# PHY.net
KiCad netlist of a schematic drawn in Altium Designer
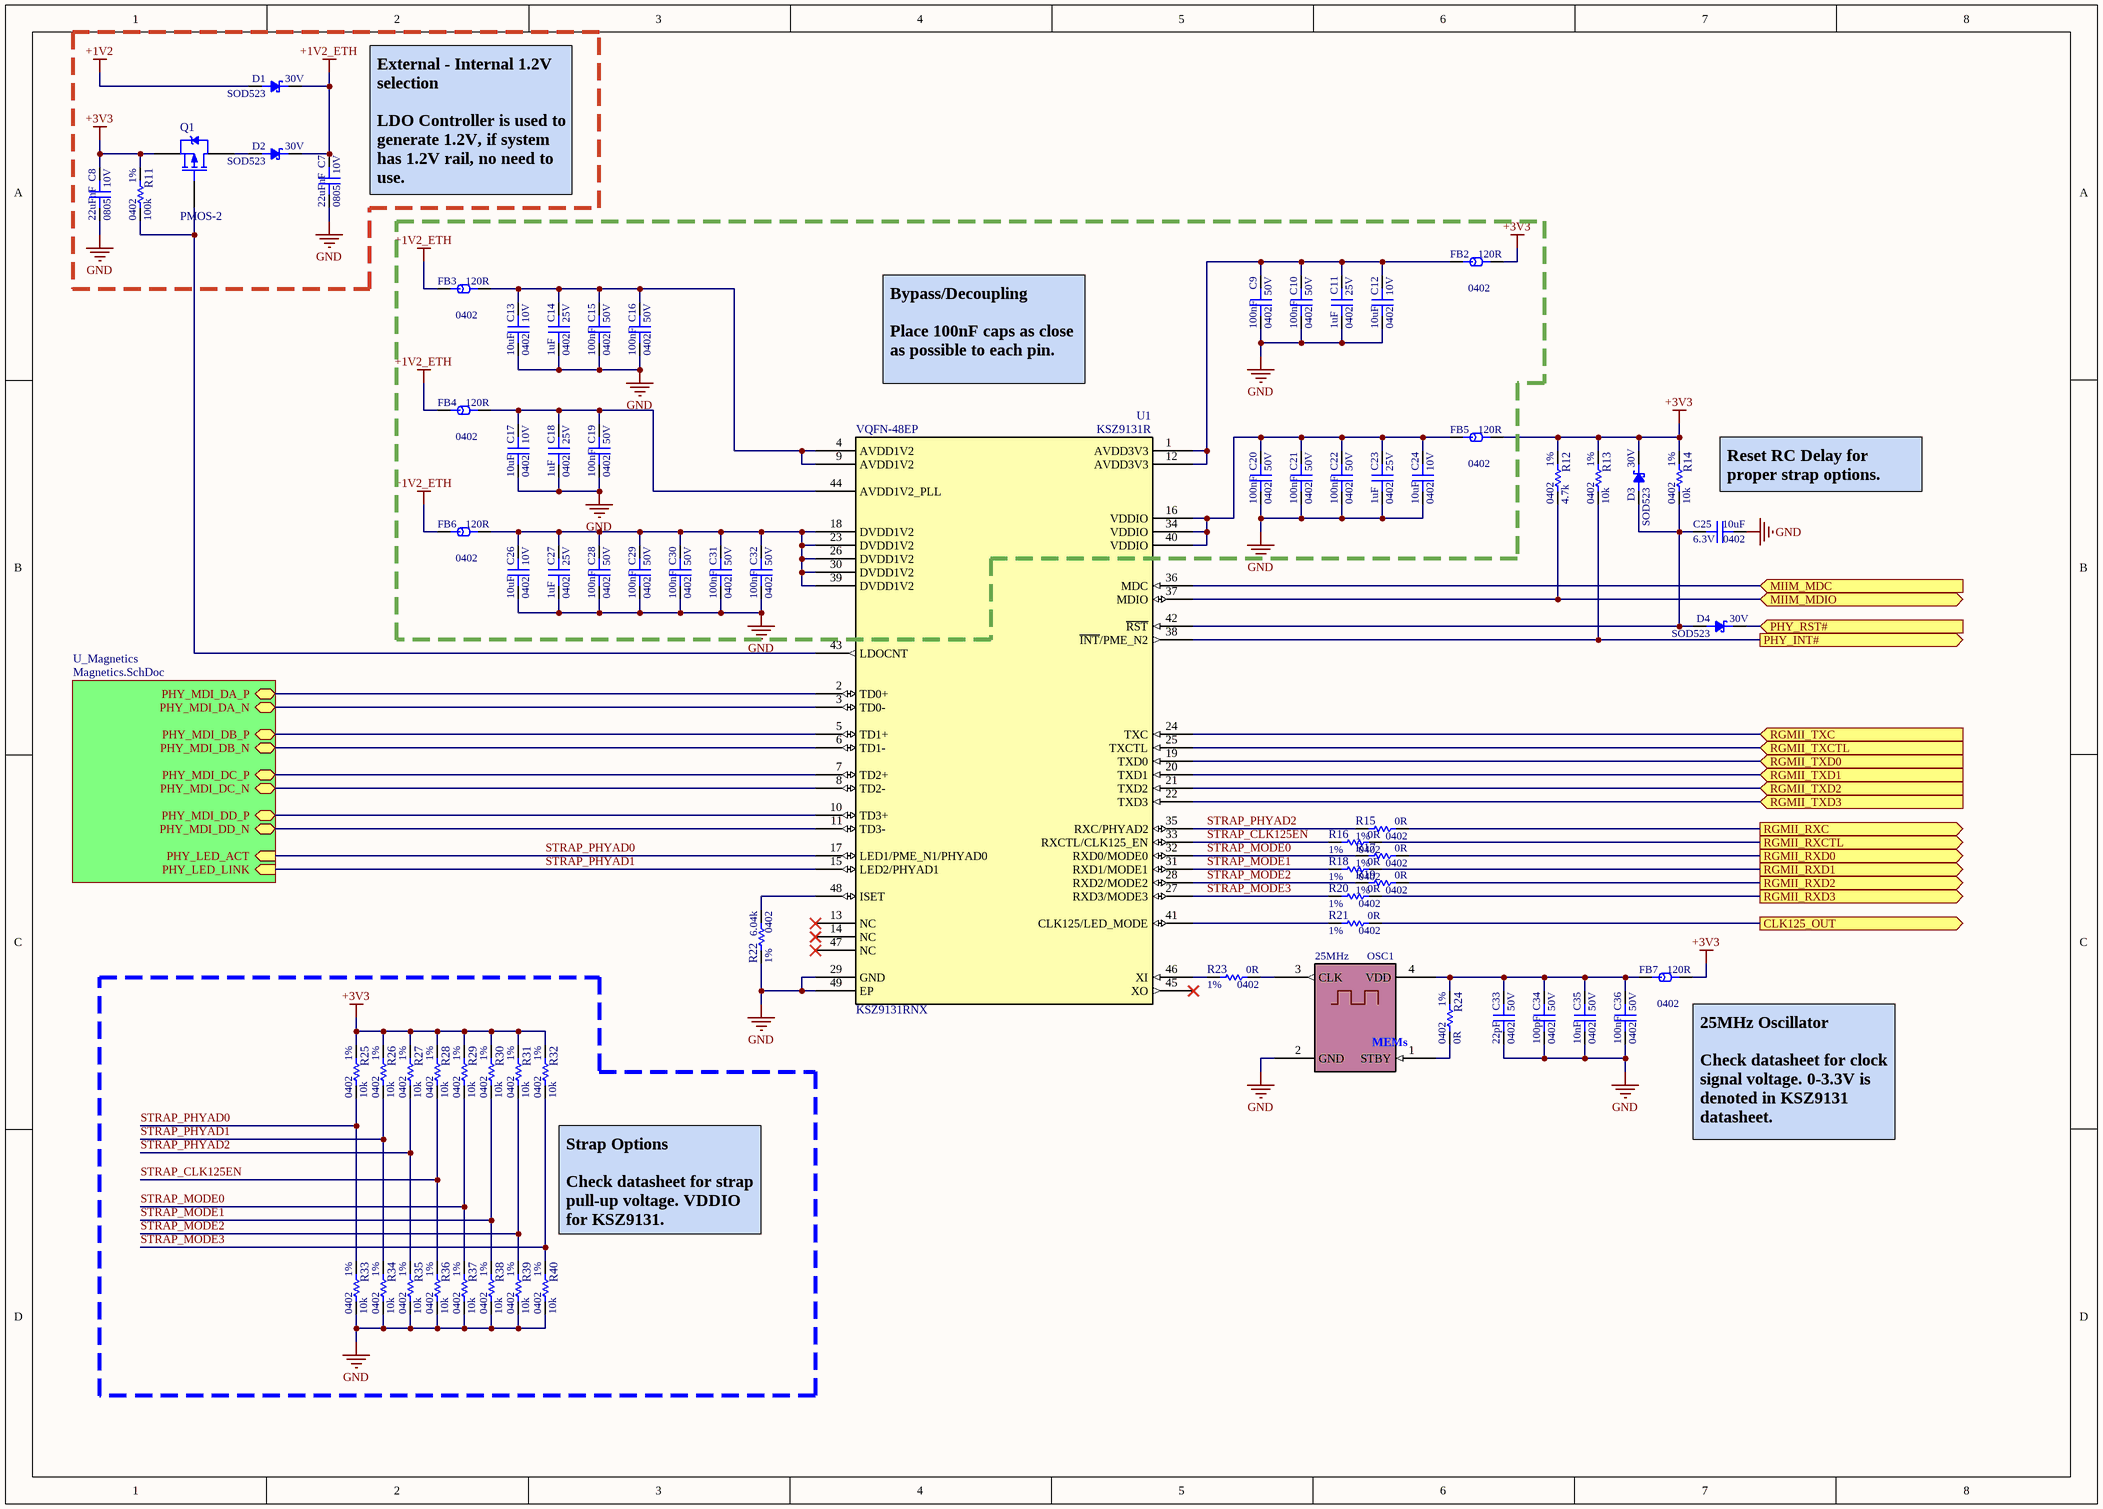
[diagram p0: PHY.SchDoc]

(export (version "E")
  (design (tool "Eeschema 10.0.6"))
  (components
    (comp (ref "C7")
      (value "22uFnF")
      (footprint "C_0402_GEN_0.70H")
      (description "CAP_CER_100nF_50V_X7R_10%_0402")
      (fields
        (field (name "VOLTAGE") "10V")
        (field (name "PACKAGE") "0805")
        (field (name "TOLERANCE") "10%")
        (field (name "Comment") "Capacitor")
      )
      (libsource (lib "BNA_HwLibDB") (part "Capacitor"))
    )
    (comp (ref "C8")
      (value "22uFnF")
      (footprint "C_0402_GEN_0.70H")
      (description "CAP_CER_100nF_50V_X7R_10%_0402")
      (fields
        (field (name "VOLTAGE") "10V")
        (field (name "PACKAGE") "0805")
        (field (name "TOLERANCE") "10%")
        (field (name "Comment") "Capacitor")
      )
      (libsource (lib "BNA_HwLibDB") (part "Capacitor"))
    )
    (comp (ref "C9")
      (value "100nF")
      (footprint "C_0402_GEN_0.70H")
      (description "CAP_CER_100nF_50V_X7R_10%_0402")
      (fields
        (field (name "VOLTAGE") "50V")
        (field (name "PACKAGE") "0402")
        (field (name "TOLERANCE") "10%")
        (field (name "Comment") "Capacitor")
      )
      (libsource (lib "BNA_HwLibDB") (part "Capacitor"))
    )
    (comp (ref "C10")
      (value "100nF")
      (footprint "C_0402_GEN_0.70H")
      (description "CAP_CER_100nF_50V_X7R_10%_0402")
      (fields
        (field (name "VOLTAGE") "50V")
        (field (name "PACKAGE") "0402")
        (field (name "TOLERANCE") "10%")
        (field (name "Comment") "Capacitor")
      )
      (libsource (lib "BNA_HwLibDB") (part "Capacitor"))
    )
    (comp (ref "C11")
      (value "1uF")
      (footprint "C_0402_GEN_0.70H")
      (description "CAP_CER_100nF_50V_X7R_10%_0402")
      (fields
        (field (name "VOLTAGE") "25V")
        (field (name "PACKAGE") "0402")
        (field (name "TOLERANCE") "10%")
        (field (name "Comment") "Capacitor")
      )
      (libsource (lib "BNA_HwLibDB") (part "Capacitor"))
    )
    (comp (ref "C12")
      (value "10uF")
      (footprint "C_0402_GEN_0.70H")
      (description "CAP_CER_100nF_50V_X7R_10%_0402")
      (fields
        (field (name "VOLTAGE") "10V")
        (field (name "PACKAGE") "0402")
        (field (name "TOLERANCE") "10%")
        (field (name "Comment") "Capacitor")
      )
      (libsource (lib "BNA_HwLibDB") (part "Capacitor"))
    )
    (comp (ref "C13")
      (value "10uF")
      (footprint "C_0402_GEN_0.70H")
      (description "CAP_CER_100nF_50V_X7R_10%_0402")
      (fields
        (field (name "VOLTAGE") "10V")
        (field (name "PACKAGE") "0402")
        (field (name "TOLERANCE") "10%")
        (field (name "Comment") "Capacitor")
      )
      (libsource (lib "BNA_HwLibDB") (part "Capacitor"))
    )
    (comp (ref "C14")
      (value "1uF")
      (footprint "C_0402_GEN_0.70H")
      (description "CAP_CER_100nF_50V_X7R_10%_0402")
      (fields
        (field (name "VOLTAGE") "25V")
        (field (name "PACKAGE") "0402")
        (field (name "TOLERANCE") "10%")
        (field (name "Comment") "Capacitor")
      )
      (libsource (lib "BNA_HwLibDB") (part "Capacitor"))
    )
    (comp (ref "C15")
      (value "100nF")
      (footprint "C_0402_GEN_0.70H")
      (description "CAP_CER_100nF_50V_X7R_10%_0402")
      (fields
        (field (name "VOLTAGE") "50V")
        (field (name "PACKAGE") "0402")
        (field (name "TOLERANCE") "10%")
        (field (name "Comment") "Capacitor")
      )
      (libsource (lib "BNA_HwLibDB") (part "Capacitor"))
    )
    (comp (ref "C16")
      (value "100nF")
      (footprint "C_0402_GEN_0.70H")
      (description "CAP_CER_100nF_50V_X7R_10%_0402")
      (fields
        (field (name "VOLTAGE") "50V")
        (field (name "PACKAGE") "0402")
        (field (name "TOLERANCE") "10%")
        (field (name "Comment") "Capacitor")
      )
      (libsource (lib "BNA_HwLibDB") (part "Capacitor"))
    )
    (comp (ref "C17")
      (value "10uF")
      (footprint "C_0402_GEN_0.70H")
      (description "CAP_CER_100nF_50V_X7R_10%_0402")
      (fields
        (field (name "VOLTAGE") "10V")
        (field (name "PACKAGE") "0402")
        (field (name "TOLERANCE") "10%")
        (field (name "Comment") "Capacitor")
      )
      (libsource (lib "BNA_HwLibDB") (part "Capacitor"))
    )
    (comp (ref "C18")
      (value "1uF")
      (footprint "C_0402_GEN_0.70H")
      (description "CAP_CER_100nF_50V_X7R_10%_0402")
      (fields
        (field (name "VOLTAGE") "25V")
        (field (name "PACKAGE") "0402")
        (field (name "TOLERANCE") "10%")
        (field (name "Comment") "Capacitor")
      )
      (libsource (lib "BNA_HwLibDB") (part "Capacitor"))
    )
    (comp (ref "C19")
      (value "100nF")
      (footprint "C_0402_GEN_0.70H")
      (description "CAP_CER_100nF_50V_X7R_10%_0402")
      (fields
        (field (name "VOLTAGE") "50V")
        (field (name "PACKAGE") "0402")
        (field (name "TOLERANCE") "10%")
        (field (name "Comment") "Capacitor")
      )
      (libsource (lib "BNA_HwLibDB") (part "Capacitor"))
    )
    (comp (ref "C20")
      (value "100nF")
      (footprint "C_0402_GEN_0.70H")
      (description "CAP_CER_100nF_50V_X7R_10%_0402")
      (fields
        (field (name "VOLTAGE") "50V")
        (field (name "PACKAGE") "0402")
        (field (name "TOLERANCE") "10%")
        (field (name "Comment") "Capacitor")
      )
      (libsource (lib "BNA_HwLibDB") (part "Capacitor"))
    )
    (comp (ref "C21")
      (value "100nF")
      (footprint "C_0402_GEN_0.70H")
      (description "CAP_CER_100nF_50V_X7R_10%_0402")
      (fields
        (field (name "VOLTAGE") "50V")
        (field (name "PACKAGE") "0402")
        (field (name "TOLERANCE") "10%")
        (field (name "Comment") "Capacitor")
      )
      (libsource (lib "BNA_HwLibDB") (part "Capacitor"))
    )
    (comp (ref "C22")
      (value "100nF")
      (footprint "C_0402_GEN_0.70H")
      (description "CAP_CER_100nF_50V_X7R_10%_0402")
      (fields
        (field (name "VOLTAGE") "50V")
        (field (name "PACKAGE") "0402")
        (field (name "TOLERANCE") "10%")
        (field (name "Comment") "Capacitor")
      )
      (libsource (lib "BNA_HwLibDB") (part "Capacitor"))
    )
    (comp (ref "C23")
      (value "1uF")
      (footprint "C_0402_GEN_0.70H")
      (description "CAP_CER_100nF_50V_X7R_10%_0402")
      (fields
        (field (name "VOLTAGE") "25V")
        (field (name "PACKAGE") "0402")
        (field (name "TOLERANCE") "10%")
        (field (name "Comment") "Capacitor")
      )
      (libsource (lib "BNA_HwLibDB") (part "Capacitor"))
    )
    (comp (ref "C24")
      (value "10uF")
      (footprint "C_0402_GEN_0.70H")
      (description "CAP_CER_100nF_50V_X7R_10%_0402")
      (fields
        (field (name "VOLTAGE") "10V")
        (field (name "PACKAGE") "0402")
        (field (name "TOLERANCE") "10%")
        (field (name "Comment") "Capacitor")
      )
      (libsource (lib "BNA_HwLibDB") (part "Capacitor"))
    )
    (comp (ref "C25")
      (value "10uF")
      (footprint "C_0402_MED-N_0.70H")
      (description "CAP_CER_10uF_6.3V_X5R_20%_0402")
      (fields
        (field (name "VOLTAGE") "6.3V")
        (field (name "PACKAGE") "0402")
        (field (name "TOLERANCE") "20%")
        (field (name "Comment") "Capacitor")
      )
      (libsource (lib "BNA_HwLibDB") (part "Capacitor"))
    )
    (comp (ref "C26")
      (value "10uF")
      (footprint "C_0402_GEN_0.70H")
      (description "CAP_CER_100nF_50V_X7R_10%_0402")
      (fields
        (field (name "VOLTAGE") "10V")
        (field (name "PACKAGE") "0402")
        (field (name "TOLERANCE") "10%")
        (field (name "Comment") "Capacitor")
      )
      (libsource (lib "BNA_HwLibDB") (part "Capacitor"))
    )
    (comp (ref "C27")
      (value "1uF")
      (footprint "C_0402_GEN_0.70H")
      (description "CAP_CER_100nF_50V_X7R_10%_0402")
      (fields
        (field (name "VOLTAGE") "25V")
        (field (name "PACKAGE") "0402")
        (field (name "TOLERANCE") "10%")
        (field (name "Comment") "Capacitor")
      )
      (libsource (lib "BNA_HwLibDB") (part "Capacitor"))
    )
    (comp (ref "C28")
      (value "100nF")
      (footprint "C_0402_GEN_0.70H")
      (description "CAP_CER_100nF_50V_X7R_10%_0402")
      (fields
        (field (name "VOLTAGE") "50V")
        (field (name "PACKAGE") "0402")
        (field (name "TOLERANCE") "10%")
        (field (name "Comment") "Capacitor")
      )
      (libsource (lib "BNA_HwLibDB") (part "Capacitor"))
    )
    (comp (ref "C29")
      (value "100nF")
      (footprint "C_0402_GEN_0.70H")
      (description "CAP_CER_100nF_50V_X7R_10%_0402")
      (fields
        (field (name "VOLTAGE") "50V")
        (field (name "PACKAGE") "0402")
        (field (name "TOLERANCE") "10%")
        (field (name "Comment") "Capacitor")
      )
      (libsource (lib "BNA_HwLibDB") (part "Capacitor"))
    )
    (comp (ref "C30")
      (value "100nF")
      (footprint "C_0402_GEN_0.70H")
      (description "CAP_CER_100nF_50V_X7R_10%_0402")
      (fields
        (field (name "VOLTAGE") "50V")
        (field (name "PACKAGE") "0402")
        (field (name "TOLERANCE") "10%")
        (field (name "Comment") "Capacitor")
      )
      (libsource (lib "BNA_HwLibDB") (part "Capacitor"))
    )
    (comp (ref "C31")
      (value "100nF")
      (footprint "C_0402_GEN_0.70H")
      (description "CAP_CER_100nF_50V_X7R_10%_0402")
      (fields
        (field (name "VOLTAGE") "50V")
        (field (name "PACKAGE") "0402")
        (field (name "TOLERANCE") "10%")
        (field (name "Comment") "Capacitor")
      )
      (libsource (lib "BNA_HwLibDB") (part "Capacitor"))
    )
    (comp (ref "C32")
      (value "100nF")
      (footprint "C_0402_GEN_0.70H")
      (description "CAP_CER_100nF_50V_X7R_10%_0402")
      (fields
        (field (name "VOLTAGE") "50V")
        (field (name "PACKAGE") "0402")
        (field (name "TOLERANCE") "10%")
        (field (name "Comment") "Capacitor")
      )
      (libsource (lib "BNA_HwLibDB") (part "Capacitor"))
    )
    (comp (ref "C33")
      (value "22pF")
      (footprint "C_0402_GEN_0.70H")
      (description "CAP_CER_10nF_50V_X7R_10%_0402")
      (fields
        (field (name "VOLTAGE") "50V")
        (field (name "PACKAGE") "0402")
        (field (name "TOLERANCE") "10%")
        (field (name "Comment") "Capacitor")
      )
      (libsource (lib "BNA_HwLibDB") (part "Capacitor"))
    )
    (comp (ref "C34")
      (value "100pF")
      (footprint "C_0402_GEN_0.70H")
      (description "CAP_CER_10nF_50V_X7R_10%_0402")
      (fields
        (field (name "VOLTAGE") "50V")
        (field (name "PACKAGE") "0402")
        (field (name "TOLERANCE") "10%")
        (field (name "Comment") "Capacitor")
      )
      (libsource (lib "BNA_HwLibDB") (part "Capacitor"))
    )
    (comp (ref "C35")
      (value "10nF")
      (footprint "C_0402_GEN_0.70H")
      (description "CAP_CER_10nF_50V_X7R_10%_0402")
      (fields
        (field (name "VOLTAGE") "50V")
        (field (name "PACKAGE") "0402")
        (field (name "TOLERANCE") "10%")
        (field (name "Comment") "Capacitor")
      )
      (libsource (lib "BNA_HwLibDB") (part "Capacitor"))
    )
    (comp (ref "C36")
      (value "100nF")
      (footprint "C_0402_GEN_0.70H")
      (description "CAP_CER_100nF_50V_X7R_10%_0402")
      (fields
        (field (name "VOLTAGE") "50V")
        (field (name "PACKAGE") "0402")
        (field (name "TOLERANCE") "10%")
        (field (name "Comment") "Capacitor")
      )
      (libsource (lib "BNA_HwLibDB") (part "Capacitor"))
    )
    (comp (ref "D1")
      (value "SchDiode_A1C2")
      (footprint "SOD523_RB530SM-30T2R")
      (description "DIO_SCHO_SING_30V_0.2A_SOD523")
      (fields (field (name "VOLTAGE") "30V") (field (name "PACKAGE") "SOD523") (field (name "TOLERANCE") "X"))
      (libsource (lib "BNA_HwLibDB") (part "SchDiode_A1C2"))
    )
    (comp (ref "D2")
      (value "SchDiode_A1C2")
      (footprint "SOD523_RB530SM-30T2R")
      (description "DIO_SCHO_SING_30V_0.2A_SOD523")
      (fields (field (name "VOLTAGE") "30V") (field (name "PACKAGE") "SOD523") (field (name "TOLERANCE") "X"))
      (libsource (lib "BNA_HwLibDB") (part "SchDiode_A1C2"))
    )
    (comp (ref "D3")
      (value "SchDiode_A1C2")
      (footprint "SOD523_RB530SM-30T2R")
      (description "DIO_SCHO_SING_30V_0.2A_SOD523")
      (fields (field (name "VOLTAGE") "30V") (field (name "PACKAGE") "SOD523") (field (name "TOLERANCE") "X"))
      (libsource (lib "BNA_HwLibDB") (part "SchDiode_A1C2"))
    )
    (comp (ref "D4")
      (value "SchDiode_A1C2")
      (footprint "SOD523_RB530SM-30T2R")
      (description "DIO_SCHO_SING_30V_0.2A_SOD523")
      (fields (field (name "VOLTAGE") "30V") (field (name "PACKAGE") "SOD523") (field (name "TOLERANCE") "X"))
      (libsource (lib "BNA_HwLibDB") (part "SchDiode_A1C2"))
    )
    (comp (ref "FB2")
      (value "120R")
      (footprint "FB_0402_GEN_0.55h")
      (description "IND_FER_120R@100M_1.3A_25%_0402")
      (fields (field (name "PACKAGE") "0402") (field (name "TOLERANCE") "±25%") (field (name "VOLTAGE") "X"))
      (libsource (lib "BNA_HwLibDB") (part "FerriteBead"))
    )
    (comp (ref "FB3")
      (value "120R")
      (footprint "FB_0402_GEN_0.55h")
      (description "IND_FER_120R@100M_1.3A_25%_0402")
      (fields (field (name "PACKAGE") "0402") (field (name "TOLERANCE") "±25%") (field (name "VOLTAGE") "X"))
      (libsource (lib "BNA_HwLibDB") (part "FerriteBead"))
    )
    (comp (ref "FB4")
      (value "120R")
      (footprint "FB_0402_GEN_0.55h")
      (description "IND_FER_120R@100M_1.3A_25%_0402")
      (fields (field (name "PACKAGE") "0402") (field (name "TOLERANCE") "±25%") (field (name "VOLTAGE") "X"))
      (libsource (lib "BNA_HwLibDB") (part "FerriteBead"))
    )
    (comp (ref "FB5")
      (value "120R")
      (footprint "FB_0402_GEN_0.55h")
      (description "IND_FER_120R@100M_1.3A_25%_0402")
      (fields (field (name "PACKAGE") "0402") (field (name "TOLERANCE") "±25%") (field (name "VOLTAGE") "X"))
      (libsource (lib "BNA_HwLibDB") (part "FerriteBead"))
    )
    (comp (ref "FB6")
      (value "120R")
      (footprint "FB_0402_GEN_0.55h")
      (description "IND_FER_120R@100M_1.3A_25%_0402")
      (fields (field (name "PACKAGE") "0402") (field (name "TOLERANCE") "±25%") (field (name "VOLTAGE") "X"))
      (libsource (lib "BNA_HwLibDB") (part "FerriteBead"))
    )
    (comp (ref "FB7")
      (value "120R")
      (footprint "FB_0402_GEN_0.55h")
      (description "IND_FER_120R@100M_1.3A_25%_0402")
      (fields (field (name "PACKAGE") "0402") (field (name "TOLERANCE") "±25%") (field (name "VOLTAGE") "X"))
      (libsource (lib "BNA_HwLibDB") (part "FerriteBead"))
    )
    (comp (ref "OSC1")
      (value "25MHz")
      (footprint "SMD_3.2X2.5X0.9_ASEMB-25.000MHZ-LY-T")
      (description "OSC_XO_25.000MHZ_10PPM_1.8V~3.3V_15pF_CMOS_3.2x2.5x0.9-SMD")
      (fields (field (name "VOLTAGE") "1.8V~3.3V") (field (name "TOLERANCE") "±10ppm"))
      (libsource (lib "BNA_HwLibDB") (part "Oscillator_4Pin"))
    )
    (comp (ref "Q1")
      (value "PMOS-2")
      (footprint "TO-220AB")
      (description "P-Channel Power MOSFET")
      (fields (field (name "PUBLISHER") "Altium Limited"))
      (libsource (lib "Miscellaneous Devices") (part "PMOS-2"))
    )
    (comp (ref "R11")
      (value "100k")
      (footprint "R_0402_GEN_0.40H")
      (description "RES_STD_100R_0.063W_1%_100ppm_0402")
      (fields
        (field (name "TOLERANCE") "1%")
        (field (name "PACKAGE") "0402")
        (field (name "VOLTAGE") "50V")
        (field (name "Comment") "StandardResistor")
      )
      (libsource (lib "BNA_HwLibDB") (part "StandardResistor"))
    )
    (comp (ref "R12")
      (value "4.7k")
      (footprint "R_0402_GEN_0.40H")
      (description "RES_STD_100R_0.063W_1%_100ppm_0402")
      (fields
        (field (name "TOLERANCE") "1%")
        (field (name "PACKAGE") "0402")
        (field (name "VOLTAGE") "50V")
        (field (name "Comment") "StandardResistor")
      )
      (libsource (lib "BNA_HwLibDB") (part "StandardResistor"))
    )
    (comp (ref "R13")
      (value "10k")
      (footprint "R_0402_GEN_0.40H")
      (description "RES_STD_100R_0.063W_1%_100ppm_0402")
      (fields
        (field (name "TOLERANCE") "1%")
        (field (name "PACKAGE") "0402")
        (field (name "VOLTAGE") "50V")
        (field (name "Comment") "StandardResistor")
      )
      (libsource (lib "BNA_HwLibDB") (part "StandardResistor"))
    )
    (comp (ref "R14")
      (value "10k")
      (footprint "R_0402_GEN_0.40H")
      (description "RES_STD_100R_0.063W_1%_100ppm_0402")
      (fields
        (field (name "TOLERANCE") "1%")
        (field (name "PACKAGE") "0402")
        (field (name "VOLTAGE") "50V")
        (field (name "Comment") "StandardResistor")
      )
      (libsource (lib "BNA_HwLibDB") (part "StandardResistor"))
    )
    (comp (ref "R15")
      (value "0R")
      (footprint "R_0402_GEN_0.40H")
      (description "RES_STD_100R_0.063W_1%_100ppm_0402")
      (fields
        (field (name "TOLERANCE") "1%")
        (field (name "PACKAGE") "0402")
        (field (name "VOLTAGE") "50V")
        (field (name "Comment") "StandardResistor")
      )
      (libsource (lib "BNA_HwLibDB") (part "StandardResistor"))
    )
    (comp (ref "R16")
      (value "0R")
      (footprint "R_0402_GEN_0.40H")
      (description "RES_STD_100R_0.063W_1%_100ppm_0402")
      (fields
        (field (name "TOLERANCE") "1%")
        (field (name "PACKAGE") "0402")
        (field (name "VOLTAGE") "50V")
        (field (name "Comment") "StandardResistor")
      )
      (libsource (lib "BNA_HwLibDB") (part "StandardResistor"))
    )
    (comp (ref "R17")
      (value "0R")
      (footprint "R_0402_GEN_0.40H")
      (description "RES_STD_100R_0.063W_1%_100ppm_0402")
      (fields
        (field (name "TOLERANCE") "1%")
        (field (name "PACKAGE") "0402")
        (field (name "VOLTAGE") "50V")
        (field (name "Comment") "StandardResistor")
      )
      (libsource (lib "BNA_HwLibDB") (part "StandardResistor"))
    )
    (comp (ref "R18")
      (value "0R")
      (footprint "R_0402_GEN_0.40H")
      (description "RES_STD_100R_0.063W_1%_100ppm_0402")
      (fields
        (field (name "TOLERANCE") "1%")
        (field (name "PACKAGE") "0402")
        (field (name "VOLTAGE") "50V")
        (field (name "Comment") "StandardResistor")
      )
      (libsource (lib "BNA_HwLibDB") (part "StandardResistor"))
    )
    (comp (ref "R19")
      (value "0R")
      (footprint "R_0402_GEN_0.40H")
      (description "RES_STD_100R_0.063W_1%_100ppm_0402")
      (fields
        (field (name "TOLERANCE") "1%")
        (field (name "PACKAGE") "0402")
        (field (name "VOLTAGE") "50V")
        (field (name "Comment") "StandardResistor")
      )
      (libsource (lib "BNA_HwLibDB") (part "StandardResistor"))
    )
    (comp (ref "R20")
      (value "0R")
      (footprint "R_0402_GEN_0.40H")
      (description "RES_STD_100R_0.063W_1%_100ppm_0402")
      (fields
        (field (name "TOLERANCE") "1%")
        (field (name "PACKAGE") "0402")
        (field (name "VOLTAGE") "50V")
        (field (name "Comment") "StandardResistor")
      )
      (libsource (lib "BNA_HwLibDB") (part "StandardResistor"))
    )
    (comp (ref "R21")
      (value "0R")
      (footprint "R_0402_GEN_0.40H")
      (description "RES_STD_100R_0.063W_1%_100ppm_0402")
      (fields
        (field (name "TOLERANCE") "1%")
        (field (name "PACKAGE") "0402")
        (field (name "VOLTAGE") "50V")
        (field (name "Comment") "StandardResistor")
      )
      (libsource (lib "BNA_HwLibDB") (part "StandardResistor"))
    )
    (comp (ref "R22")
      (value "6.04k")
      (footprint "R_0402_GEN_0.40H")
      (description "RES_STD_100R_0.063W_1%_100ppm_0402")
      (fields
        (field (name "TOLERANCE") "1%")
        (field (name "PACKAGE") "0402")
        (field (name "VOLTAGE") "50V")
        (field (name "Comment") "StandardResistor")
      )
      (libsource (lib "BNA_HwLibDB") (part "StandardResistor"))
    )
    (comp (ref "R23")
      (value "0R")
      (footprint "R_0402_GEN_0.40H")
      (description "RES_STD_100R_0.063W_1%_100ppm_0402")
      (fields
        (field (name "TOLERANCE") "1%")
        (field (name "PACKAGE") "0402")
        (field (name "VOLTAGE") "50V")
        (field (name "Comment") "StandardResistor")
      )
      (libsource (lib "BNA_HwLibDB") (part "StandardResistor"))
    )
    (comp (ref "R24")
      (value "0R")
      (footprint "R_0402_GEN_0.40H")
      (description "RES_STD_100R_0.063W_1%_100ppm_0402")
      (fields
        (field (name "TOLERANCE") "1%")
        (field (name "PACKAGE") "0402")
        (field (name "VOLTAGE") "50V")
        (field (name "Comment") "StandardResistor")
      )
      (libsource (lib "BNA_HwLibDB") (part "StandardResistor"))
    )
    (comp (ref "R25")
      (value "10k")
      (footprint "R_0402_GEN_0.40H")
      (description "RES_STD_100R_0.063W_1%_100ppm_0402")
      (fields
        (field (name "TOLERANCE") "1%")
        (field (name "PACKAGE") "0402")
        (field (name "VOLTAGE") "50V")
        (field (name "Comment") "StandardResistor")
      )
      (libsource (lib "BNA_HwLibDB") (part "StandardResistor"))
    )
    (comp (ref "R26")
      (value "10k")
      (footprint "R_0402_GEN_0.40H")
      (description "RES_STD_100R_0.063W_1%_100ppm_0402")
      (fields
        (field (name "TOLERANCE") "1%")
        (field (name "PACKAGE") "0402")
        (field (name "VOLTAGE") "50V")
        (field (name "Comment") "StandardResistor")
      )
      (libsource (lib "BNA_HwLibDB") (part "StandardResistor"))
    )
    (comp (ref "R27")
      (value "10k")
      (footprint "R_0402_GEN_0.40H")
      (description "RES_STD_100R_0.063W_1%_100ppm_0402")
      (fields
        (field (name "TOLERANCE") "1%")
        (field (name "PACKAGE") "0402")
        (field (name "VOLTAGE") "50V")
        (field (name "Comment") "StandardResistor")
      )
      (libsource (lib "BNA_HwLibDB") (part "StandardResistor"))
    )
    (comp (ref "R28")
      (value "10k")
      (footprint "R_0402_GEN_0.40H")
      (description "RES_STD_100R_0.063W_1%_100ppm_0402")
      (fields
        (field (name "TOLERANCE") "1%")
        (field (name "PACKAGE") "0402")
        (field (name "VOLTAGE") "50V")
        (field (name "Comment") "StandardResistor")
      )
      (libsource (lib "BNA_HwLibDB") (part "StandardResistor"))
    )
    (comp (ref "R29")
      (value "10k")
      (footprint "R_0402_GEN_0.40H")
      (description "RES_STD_100R_0.063W_1%_100ppm_0402")
      (fields
        (field (name "TOLERANCE") "1%")
        (field (name "PACKAGE") "0402")
        (field (name "VOLTAGE") "50V")
        (field (name "Comment") "StandardResistor")
      )
      (libsource (lib "BNA_HwLibDB") (part "StandardResistor"))
    )
    (comp (ref "R30")
      (value "10k")
      (footprint "R_0402_GEN_0.40H")
      (description "RES_STD_100R_0.063W_1%_100ppm_0402")
      (fields
        (field (name "TOLERANCE") "1%")
        (field (name "PACKAGE") "0402")
        (field (name "VOLTAGE") "50V")
        (field (name "Comment") "StandardResistor")
      )
      (libsource (lib "BNA_HwLibDB") (part "StandardResistor"))
    )
    (comp (ref "R31")
      (value "10k")
      (footprint "R_0402_GEN_0.40H")
      (description "RES_STD_100R_0.063W_1%_100ppm_0402")
      (fields
        (field (name "TOLERANCE") "1%")
        (field (name "PACKAGE") "0402")
        (field (name "VOLTAGE") "50V")
        (field (name "Comment") "StandardResistor")
      )
      (libsource (lib "BNA_HwLibDB") (part "StandardResistor"))
    )
    (comp (ref "R32")
      (value "10k")
      (footprint "R_0402_GEN_0.40H")
      (description "RES_STD_100R_0.063W_1%_100ppm_0402")
      (fields
        (field (name "TOLERANCE") "1%")
        (field (name "PACKAGE") "0402")
        (field (name "VOLTAGE") "50V")
        (field (name "Comment") "StandardResistor")
      )
      (libsource (lib "BNA_HwLibDB") (part "StandardResistor"))
    )
    (comp (ref "R33")
      (value "10k")
      (footprint "R_0402_GEN_0.40H")
      (description "RES_STD_100R_0.063W_1%_100ppm_0402")
      (fields
        (field (name "TOLERANCE") "1%")
        (field (name "PACKAGE") "0402")
        (field (name "VOLTAGE") "50V")
        (field (name "Comment") "StandardResistor")
      )
      (libsource (lib "BNA_HwLibDB") (part "StandardResistor"))
    )
    (comp (ref "R34")
      (value "10k")
      (footprint "R_0402_GEN_0.40H")
      (description "RES_STD_100R_0.063W_1%_100ppm_0402")
      (fields
        (field (name "TOLERANCE") "1%")
        (field (name "PACKAGE") "0402")
        (field (name "VOLTAGE") "50V")
        (field (name "Comment") "StandardResistor")
      )
      (libsource (lib "BNA_HwLibDB") (part "StandardResistor"))
    )
    (comp (ref "R35")
      (value "10k")
      (footprint "R_0402_GEN_0.40H")
      (description "RES_STD_100R_0.063W_1%_100ppm_0402")
      (fields
        (field (name "TOLERANCE") "1%")
        (field (name "PACKAGE") "0402")
        (field (name "VOLTAGE") "50V")
        (field (name "Comment") "StandardResistor")
      )
      (libsource (lib "BNA_HwLibDB") (part "StandardResistor"))
    )
    (comp (ref "R36")
      (value "10k")
      (footprint "R_0402_GEN_0.40H")
      (description "RES_STD_100R_0.063W_1%_100ppm_0402")
      (fields
        (field (name "TOLERANCE") "1%")
        (field (name "PACKAGE") "0402")
        (field (name "VOLTAGE") "50V")
        (field (name "Comment") "StandardResistor")
      )
      (libsource (lib "BNA_HwLibDB") (part "StandardResistor"))
    )
    (comp (ref "R37")
      (value "10k")
      (footprint "R_0402_GEN_0.40H")
      (description "RES_STD_100R_0.063W_1%_100ppm_0402")
      (fields
        (field (name "TOLERANCE") "1%")
        (field (name "PACKAGE") "0402")
        (field (name "VOLTAGE") "50V")
        (field (name "Comment") "StandardResistor")
      )
      (libsource (lib "BNA_HwLibDB") (part "StandardResistor"))
    )
    (comp (ref "R38")
      (value "10k")
      (footprint "R_0402_GEN_0.40H")
      (description "RES_STD_100R_0.063W_1%_100ppm_0402")
      (fields
        (field (name "TOLERANCE") "1%")
        (field (name "PACKAGE") "0402")
        (field (name "VOLTAGE") "50V")
        (field (name "Comment") "StandardResistor")
      )
      (libsource (lib "BNA_HwLibDB") (part "StandardResistor"))
    )
    (comp (ref "R39")
      (value "10k")
      (footprint "R_0402_GEN_0.40H")
      (description "RES_STD_100R_0.063W_1%_100ppm_0402")
      (fields
        (field (name "TOLERANCE") "1%")
        (field (name "PACKAGE") "0402")
        (field (name "VOLTAGE") "50V")
        (field (name "Comment") "StandardResistor")
      )
      (libsource (lib "BNA_HwLibDB") (part "StandardResistor"))
    )
    (comp (ref "R40")
      (value "10k")
      (footprint "R_0402_GEN_0.40H")
      (description "RES_STD_100R_0.063W_1%_100ppm_0402")
      (fields
        (field (name "TOLERANCE") "1%")
        (field (name "PACKAGE") "0402")
        (field (name "VOLTAGE") "50V")
        (field (name "Comment") "StandardResistor")
      )
      (libsource (lib "BNA_HwLibDB") (part "StandardResistor"))
    )
    (comp (ref "U1")
      (value "KSZ9131RNX")
      (description "GBit Eth Phy w/RGMII Interface")
      (fields
        (field (name "VOLTAGE") "voltage")
        (field (name "ALTIUM_VALUE") "KSZ9131R")
        (field (name "PACKAGE") "VQFN-48EP")
      )
      (libsource (lib "KSZ9131RNX") (part "KSZ9131RNX"))
    )
  )
  (nets
    (net (code "1") (name "+1V2") (class "Default")
      (node (ref "D1") (pin "1") (pinfunction "A_1") (pintype "passive"))
    )
    (net (code "2") (name "+1V2_ETH") (class "Default")
      (node (ref "C7") (pin "1") (pinfunction "1_1") (pintype "passive"))
      (node (ref "D1") (pin "2") (pinfunction "C_2") (pintype "passive"))
      (node (ref "D2") (pin "2") (pinfunction "C_2") (pintype "passive"))
      (node (ref "FB3") (pin "1") (pinfunction "1_1") (pintype "passive"))
      (node (ref "FB4") (pin "1") (pinfunction "1_1") (pintype "passive"))
      (node (ref "FB6") (pin "1") (pinfunction "1_1") (pintype "passive"))
    )
    (net (code "3") (name "+3V3") (class "Default")
      (node (ref "C8") (pin "1") (pinfunction "1_1") (pintype "passive"))
      (node (ref "D3") (pin "2") (pinfunction "C_2") (pintype "passive"))
      (node (ref "FB2") (pin "2") (pinfunction "2_2") (pintype "passive"))
      (node (ref "FB5") (pin "2") (pinfunction "2_2") (pintype "passive"))
      (node (ref "FB7") (pin "2") (pinfunction "2_2") (pintype "passive"))
      (node (ref "Q1") (pin "3") (pinfunction "S_3") (pintype "passive"))
      (node (ref "R11") (pin "1") (pinfunction "1_1") (pintype "passive"))
      (node (ref "R12") (pin "1") (pinfunction "1_1") (pintype "passive"))
      (node (ref "R13") (pin "1") (pinfunction "1_1") (pintype "passive"))
      (node (ref "R14") (pin "1") (pinfunction "1_1") (pintype "passive"))
      (node (ref "R25") (pin "1") (pinfunction "1_1") (pintype "passive"))
      (node (ref "R26") (pin "1") (pinfunction "1_1") (pintype "passive"))
      (node (ref "R27") (pin "1") (pinfunction "1_1") (pintype "passive"))
      (node (ref "R28") (pin "1") (pinfunction "1_1") (pintype "passive"))
      (node (ref "R29") (pin "1") (pinfunction "1_1") (pintype "passive"))
      (node (ref "R30") (pin "1") (pinfunction "1_1") (pintype "passive"))
      (node (ref "R31") (pin "1") (pinfunction "1_1") (pintype "passive"))
      (node (ref "R32") (pin "1") (pinfunction "1_1") (pintype "passive"))
    )
    (net (code "4") (name "/CLK125_OUT") (class "Default")
      (node (ref "R21") (pin "2") (pinfunction "2_2") (pintype "passive"))
    )
    (net (code "5") (name "/MIIM_MDC") (class "Default")
      (node (ref "U1") (pin "36") (pinfunction "MDC_36") (pintype "input"))
    )
    (net (code "6") (name "/MIIM_MDIO") (class "Default")
      (node (ref "R12") (pin "2") (pinfunction "2_2") (pintype "passive"))
      (node (ref "U1") (pin "37") (pinfunction "MDIO_37") (pintype "bidirectional"))
    )
    (net (code "7") (name "/PHY_INT#") (class "Default")
      (node (ref "R13") (pin "2") (pinfunction "2_2") (pintype "passive"))
      (node (ref "U1") (pin "38") (pinfunction "~{INT}/PME_N2_38") (pintype "output"))
    )
    (net (code "8") (name "/PHY_MDI_DA_N") (class "Default")
      (node (ref "U1") (pin "3") (pinfunction "TD0-_3") (pintype "bidirectional"))
    )
    (net (code "9") (name "/PHY_MDI_DA_P") (class "Default")
      (node (ref "U1") (pin "2") (pinfunction "TD0+_2") (pintype "bidirectional"))
    )
    (net (code "10") (name "/PHY_MDI_DB_N") (class "Default")
      (node (ref "U1") (pin "6") (pinfunction "TD1-_6") (pintype "bidirectional"))
    )
    (net (code "11") (name "/PHY_MDI_DB_P") (class "Default")
      (node (ref "U1") (pin "5") (pinfunction "TD1+_5") (pintype "bidirectional"))
    )
    (net (code "12") (name "/PHY_MDI_DC_N") (class "Default")
      (node (ref "U1") (pin "8") (pinfunction "TD2-_8") (pintype "bidirectional"))
    )
    (net (code "13") (name "/PHY_MDI_DC_P") (class "Default")
      (node (ref "U1") (pin "7") (pinfunction "TD2+_7") (pintype "bidirectional"))
    )
    (net (code "14") (name "/PHY_MDI_DD_N") (class "Default")
      (node (ref "U1") (pin "11") (pinfunction "TD3-_11") (pintype "bidirectional"))
    )
    (net (code "15") (name "/PHY_MDI_DD_P") (class "Default")
      (node (ref "U1") (pin "10") (pinfunction "TD3+_10") (pintype "bidirectional"))
    )
    (net (code "16") (name "/PHY_RST#") (class "Default")
      (node (ref "D4") (pin "2") (pinfunction "C_2") (pintype "passive"))
    )
    (net (code "17") (name "/RGMII_RXC") (class "Default")
      (node (ref "R15") (pin "2") (pinfunction "2_2") (pintype "passive"))
    )
    (net (code "18") (name "/RGMII_RXCTL") (class "Default")
      (node (ref "R16") (pin "2") (pinfunction "2_2") (pintype "passive"))
    )
    (net (code "19") (name "/RGMII_RXD0") (class "Default")
      (node (ref "R17") (pin "2") (pinfunction "2_2") (pintype "passive"))
    )
    (net (code "20") (name "/RGMII_RXD1") (class "Default")
      (node (ref "R18") (pin "2") (pinfunction "2_2") (pintype "passive"))
    )
    (net (code "21") (name "/RGMII_RXD2") (class "Default")
      (node (ref "R19") (pin "2") (pinfunction "2_2") (pintype "passive"))
    )
    (net (code "22") (name "/RGMII_RXD3") (class "Default")
      (node (ref "R20") (pin "2") (pinfunction "2_2") (pintype "passive"))
    )
    (net (code "23") (name "/RGMII_TXC") (class "Default")
      (node (ref "U1") (pin "24") (pinfunction "TXC_24") (pintype "input"))
    )
    (net (code "24") (name "/RGMII_TXCTL") (class "Default")
      (node (ref "U1") (pin "25") (pinfunction "TXCTL_25") (pintype "input"))
    )
    (net (code "25") (name "/RGMII_TXD0") (class "Default")
      (node (ref "U1") (pin "19") (pinfunction "TXD0_19") (pintype "input"))
    )
    (net (code "26") (name "/RGMII_TXD1") (class "Default")
      (node (ref "U1") (pin "20") (pinfunction "TXD1_20") (pintype "input"))
    )
    (net (code "27") (name "/RGMII_TXD2") (class "Default")
      (node (ref "U1") (pin "21") (pinfunction "TXD2_21") (pintype "input"))
    )
    (net (code "28") (name "/RGMII_TXD3") (class "Default")
      (node (ref "U1") (pin "22") (pinfunction "TXD3_22") (pintype "input"))
    )
    (net (code "29") (name "/STRAP_CLK125EN") (class "Default")
      (node (ref "R16") (pin "1") (pinfunction "1_1") (pintype "passive"))
      (node (ref "R28") (pin "2") (pinfunction "2_2") (pintype "passive"))
      (node (ref "R36") (pin "1") (pinfunction "1_1") (pintype "passive"))
      (node (ref "U1") (pin "33") (pinfunction "RXCTL/CLK125_EN_33") (pintype "bidirectional"))
    )
    (net (code "30") (name "/STRAP_MODE0") (class "Default")
      (node (ref "R17") (pin "1") (pinfunction "1_1") (pintype "passive"))
      (node (ref "R29") (pin "2") (pinfunction "2_2") (pintype "passive"))
      (node (ref "R37") (pin "1") (pinfunction "1_1") (pintype "passive"))
      (node (ref "U1") (pin "32") (pinfunction "RXD0/MODE0_32") (pintype "bidirectional"))
    )
    (net (code "31") (name "/STRAP_MODE1") (class "Default")
      (node (ref "R18") (pin "1") (pinfunction "1_1") (pintype "passive"))
      (node (ref "R30") (pin "2") (pinfunction "2_2") (pintype "passive"))
      (node (ref "R38") (pin "1") (pinfunction "1_1") (pintype "passive"))
      (node (ref "U1") (pin "31") (pinfunction "RXD1/MODE1_31") (pintype "bidirectional"))
    )
    (net (code "32") (name "/STRAP_MODE2") (class "Default")
      (node (ref "R19") (pin "1") (pinfunction "1_1") (pintype "passive"))
      (node (ref "R31") (pin "2") (pinfunction "2_2") (pintype "passive"))
      (node (ref "R39") (pin "1") (pinfunction "1_1") (pintype "passive"))
      (node (ref "U1") (pin "28") (pinfunction "RXD2/MODE2_28") (pintype "bidirectional"))
    )
    (net (code "33") (name "/STRAP_MODE3") (class "Default")
      (node (ref "R20") (pin "1") (pinfunction "1_1") (pintype "passive"))
      (node (ref "R32") (pin "2") (pinfunction "2_2") (pintype "passive"))
      (node (ref "R40") (pin "1") (pinfunction "1_1") (pintype "passive"))
      (node (ref "U1") (pin "27") (pinfunction "RXD3/MODE3_27") (pintype "bidirectional"))
    )
    (net (code "34") (name "/STRAP_PHYAD0") (class "Default")
      (node (ref "R25") (pin "2") (pinfunction "2_2") (pintype "passive"))
      (node (ref "R33") (pin "1") (pinfunction "1_1") (pintype "passive"))
      (node (ref "U1") (pin "17") (pinfunction "LED1/PME_N1/PHYAD0_17") (pintype "bidirectional"))
    )
    (net (code "35") (name "/STRAP_PHYAD1") (class "Default")
      (node (ref "R26") (pin "2") (pinfunction "2_2") (pintype "passive"))
      (node (ref "R34") (pin "1") (pinfunction "1_1") (pintype "passive"))
      (node (ref "U1") (pin "15") (pinfunction "LED2/PHYAD1_15") (pintype "bidirectional"))
    )
    (net (code "36") (name "/STRAP_PHYAD2") (class "Default")
      (node (ref "R15") (pin "1") (pinfunction "1_1") (pintype "passive"))
      (node (ref "R27") (pin "2") (pinfunction "2_2") (pintype "passive"))
      (node (ref "R35") (pin "1") (pinfunction "1_1") (pintype "passive"))
      (node (ref "U1") (pin "35") (pinfunction "RXC/PHYAD2_35") (pintype "bidirectional"))
    )
    (net (code "37") (name "GND") (class "Default")
      (node (ref "C10") (pin "2") (pinfunction "2_2") (pintype "passive"))
      (node (ref "C11") (pin "2") (pinfunction "2_2") (pintype "passive"))
      (node (ref "C12") (pin "2") (pinfunction "2_2") (pintype "passive"))
      (node (ref "C13") (pin "2") (pinfunction "2_2") (pintype "passive"))
      (node (ref "C14") (pin "2") (pinfunction "2_2") (pintype "passive"))
      (node (ref "C15") (pin "2") (pinfunction "2_2") (pintype "passive"))
      (node (ref "C16") (pin "2") (pinfunction "2_2") (pintype "passive"))
      (node (ref "C17") (pin "2") (pinfunction "2_2") (pintype "passive"))
      (node (ref "C18") (pin "2") (pinfunction "2_2") (pintype "passive"))
      (node (ref "C19") (pin "2") (pinfunction "2_2") (pintype "passive"))
      (node (ref "C20") (pin "2") (pinfunction "2_2") (pintype "passive"))
      (node (ref "C21") (pin "2") (pinfunction "2_2") (pintype "passive"))
      (node (ref "C22") (pin "2") (pinfunction "2_2") (pintype "passive"))
      (node (ref "C23") (pin "2") (pinfunction "2_2") (pintype "passive"))
      (node (ref "C24") (pin "2") (pinfunction "2_2") (pintype "passive"))
      (node (ref "C25") (pin "2") (pinfunction "2_2") (pintype "passive"))
      (node (ref "C26") (pin "2") (pinfunction "2_2") (pintype "passive"))
      (node (ref "C27") (pin "2") (pinfunction "2_2") (pintype "passive"))
      (node (ref "C28") (pin "2") (pinfunction "2_2") (pintype "passive"))
      (node (ref "C29") (pin "2") (pinfunction "2_2") (pintype "passive"))
      (node (ref "C30") (pin "2") (pinfunction "2_2") (pintype "passive"))
      (node (ref "C31") (pin "2") (pinfunction "2_2") (pintype "passive"))
      (node (ref "C32") (pin "2") (pinfunction "2_2") (pintype "passive"))
      (node (ref "C33") (pin "2") (pinfunction "2_2") (pintype "passive"))
      (node (ref "C34") (pin "2") (pinfunction "2_2") (pintype "passive"))
      (node (ref "C35") (pin "2") (pinfunction "2_2") (pintype "passive"))
      (node (ref "C36") (pin "2") (pinfunction "2_2") (pintype "passive"))
      (node (ref "C7") (pin "2") (pinfunction "2_2") (pintype "passive"))
      (node (ref "C8") (pin "2") (pinfunction "2_2") (pintype "passive"))
      (node (ref "C9") (pin "2") (pinfunction "2_2") (pintype "passive"))
      (node (ref "OSC1") (pin "2") (pinfunction "GND_2") (pintype "power_in"))
      (node (ref "R22") (pin "1") (pinfunction "1_1") (pintype "passive"))
      (node (ref "R33") (pin "2") (pinfunction "2_2") (pintype "passive"))
      (node (ref "R34") (pin "2") (pinfunction "2_2") (pintype "passive"))
      (node (ref "R35") (pin "2") (pinfunction "2_2") (pintype "passive"))
      (node (ref "R36") (pin "2") (pinfunction "2_2") (pintype "passive"))
      (node (ref "R37") (pin "2") (pinfunction "2_2") (pintype "passive"))
      (node (ref "R38") (pin "2") (pinfunction "2_2") (pintype "passive"))
      (node (ref "R39") (pin "2") (pinfunction "2_2") (pintype "passive"))
      (node (ref "R40") (pin "2") (pinfunction "2_2") (pintype "passive"))
      (node (ref "U1") (pin "29") (pinfunction "GND_29") (pintype "power_in"))
      (node (ref "U1") (pin "49") (pinfunction "EP_49") (pintype "power_in"))
    )
    (net (code "38") (name "Net-(C10-Pad1)") (class "Default")
      (node (ref "C10") (pin "1") (pinfunction "1_1") (pintype "passive"))
      (node (ref "C11") (pin "1") (pinfunction "1_1") (pintype "passive"))
      (node (ref "C12") (pin "1") (pinfunction "1_1") (pintype "passive"))
      (node (ref "C9") (pin "1") (pinfunction "1_1") (pintype "passive"))
      (node (ref "FB2") (pin "1") (pinfunction "1_1") (pintype "passive"))
      (node (ref "U1") (pin "1") (pinfunction "AVDD3V3_1") (pintype "power_in"))
      (node (ref "U1") (pin "12") (pinfunction "AVDD3V3_12") (pintype "power_in"))
    )
    (net (code "39") (name "Net-(C13-Pad1)") (class "Default")
      (node (ref "C13") (pin "1") (pinfunction "1_1") (pintype "passive"))
      (node (ref "C14") (pin "1") (pinfunction "1_1") (pintype "passive"))
      (node (ref "C15") (pin "1") (pinfunction "1_1") (pintype "passive"))
      (node (ref "C16") (pin "1") (pinfunction "1_1") (pintype "passive"))
      (node (ref "FB3") (pin "2") (pinfunction "2_2") (pintype "passive"))
      (node (ref "U1") (pin "4") (pinfunction "AVDD1V2_4") (pintype "power_in"))
      (node (ref "U1") (pin "9") (pinfunction "AVDD1V2_9") (pintype "power_in"))
    )
    (net (code "40") (name "Net-(C20-Pad1)") (class "Default")
      (node (ref "C20") (pin "1") (pinfunction "1_1") (pintype "passive"))
      (node (ref "C21") (pin "1") (pinfunction "1_1") (pintype "passive"))
      (node (ref "C22") (pin "1") (pinfunction "1_1") (pintype "passive"))
      (node (ref "C23") (pin "1") (pinfunction "1_1") (pintype "passive"))
      (node (ref "C24") (pin "1") (pinfunction "1_1") (pintype "passive"))
      (node (ref "FB5") (pin "1") (pinfunction "1_1") (pintype "passive"))
      (node (ref "U1") (pin "16") (pinfunction "VDDIO_16") (pintype "power_in"))
      (node (ref "U1") (pin "34") (pinfunction "VDDIO_34") (pintype "power_in"))
      (node (ref "U1") (pin "40") (pinfunction "VDDIO_40") (pintype "power_in"))
    )
    (net (code "41") (name "Net-(C26-Pad1)") (class "Default")
      (node (ref "C26") (pin "1") (pinfunction "1_1") (pintype "passive"))
      (node (ref "C27") (pin "1") (pinfunction "1_1") (pintype "passive"))
      (node (ref "C28") (pin "1") (pinfunction "1_1") (pintype "passive"))
      (node (ref "C29") (pin "1") (pinfunction "1_1") (pintype "passive"))
      (node (ref "C30") (pin "1") (pinfunction "1_1") (pintype "passive"))
      (node (ref "C31") (pin "1") (pinfunction "1_1") (pintype "passive"))
      (node (ref "C32") (pin "1") (pinfunction "1_1") (pintype "passive"))
      (node (ref "FB6") (pin "2") (pinfunction "2_2") (pintype "passive"))
      (node (ref "U1") (pin "18") (pinfunction "DVDD1V2_18") (pintype "power_in"))
      (node (ref "U1") (pin "23") (pinfunction "DVDD1V2_23") (pintype "power_in"))
      (node (ref "U1") (pin "26") (pinfunction "DVDD1V2_26") (pintype "power_in"))
      (node (ref "U1") (pin "30") (pinfunction "DVDD1V2_30") (pintype "power_in"))
      (node (ref "U1") (pin "39") (pinfunction "DVDD1V2_39") (pintype "power_in"))
    )
    (net (code "42") (name "Net-(D2-A)") (class "Default")
      (node (ref "D2") (pin "1") (pinfunction "A_1") (pintype "passive"))
      (node (ref "Q1") (pin "2") (pinfunction "D_2") (pintype "passive"))
    )
    (net (code "43") (name "Net-(D3-A)") (class "Default")
      (node (ref "C25") (pin "1") (pinfunction "1_1") (pintype "passive"))
      (node (ref "D3") (pin "1") (pinfunction "A_1") (pintype "passive"))
      (node (ref "D4") (pin "1") (pinfunction "A_1") (pintype "passive"))
      (node (ref "R14") (pin "2") (pinfunction "2_2") (pintype "passive"))
      (node (ref "U1") (pin "42") (pinfunction "~{RST}_42") (pintype "input"))
    )
    (net (code "44") (name "Net-(OSC1-CLK)") (class "Default")
      (node (ref "OSC1") (pin "3") (pinfunction "CLK_3") (pintype "output"))
      (node (ref "R23") (pin "2") (pinfunction "2_2") (pintype "passive"))
    )
    (net (code "45") (name "Net-(OSC1-STBY)") (class "Default")
      (node (ref "OSC1") (pin "1") (pinfunction "STBY_1") (pintype "input"))
      (node (ref "R24") (pin "2") (pinfunction "2_2") (pintype "passive"))
    )
    (net (code "46") (name "Net-(OSC1-VDD)") (class "Default")
      (node (ref "C33") (pin "1") (pinfunction "1_1") (pintype "passive"))
      (node (ref "C34") (pin "1") (pinfunction "1_1") (pintype "passive"))
      (node (ref "C35") (pin "1") (pinfunction "1_1") (pintype "passive"))
      (node (ref "C36") (pin "1") (pinfunction "1_1") (pintype "passive"))
      (node (ref "FB7") (pin "1") (pinfunction "1_1") (pintype "passive"))
      (node (ref "OSC1") (pin "4") (pinfunction "VDD_4") (pintype "power_in"))
      (node (ref "R24") (pin "1") (pinfunction "1_1") (pintype "passive"))
    )
    (net (code "47") (name "Net-(Q1-G)") (class "Default")
      (node (ref "Q1") (pin "1") (pinfunction "G_1") (pintype "passive"))
      (node (ref "R11") (pin "2") (pinfunction "2_2") (pintype "passive"))
      (node (ref "U1") (pin "43") (pinfunction "LDOCNT_43") (pintype "output"))
    )
    (net (code "48") (name "Net-(U1-AVDD1V2_PLL)") (class "Default")
      (node (ref "C17") (pin "1") (pinfunction "1_1") (pintype "passive"))
      (node (ref "C18") (pin "1") (pinfunction "1_1") (pintype "passive"))
      (node (ref "C19") (pin "1") (pinfunction "1_1") (pintype "passive"))
      (node (ref "FB4") (pin "2") (pinfunction "2_2") (pintype "passive"))
      (node (ref "U1") (pin "44") (pinfunction "AVDD1V2_PLL_44") (pintype "power_in"))
    )
    (net (code "49") (name "Net-(U1-CLK125{slash}LED_MODE)") (class "Default")
      (node (ref "R21") (pin "1") (pinfunction "1_1") (pintype "passive"))
      (node (ref "U1") (pin "41") (pinfunction "CLK125/LED_MODE_41") (pintype "bidirectional"))
    )
    (net (code "50") (name "Net-(U1-ISET)") (class "Default")
      (node (ref "R22") (pin "2") (pinfunction "2_2") (pintype "passive"))
      (node (ref "U1") (pin "48") (pinfunction "ISET_48") (pintype "bidirectional"))
    )
    (net (code "51") (name "Net-(U1-XI)") (class "Default")
      (node (ref "R23") (pin "1") (pinfunction "1_1") (pintype "passive"))
      (node (ref "U1") (pin "46") (pinfunction "XI_46") (pintype "input"))
    )
    (net (code "52") (name "unconnected-(U1-NC-Pad13)") (class "Default")
      (node (ref "U1") (pin "13") (pinfunction "NC_13") (pintype "passive+no_connect"))
    )
    (net (code "53") (name "unconnected-(U1-NC-Pad14)") (class "Default")
      (node (ref "U1") (pin "14") (pinfunction "NC_14") (pintype "passive+no_connect"))
    )
    (net (code "54") (name "unconnected-(U1-NC-Pad47)") (class "Default")
      (node (ref "U1") (pin "47") (pinfunction "NC_47") (pintype "passive+no_connect"))
    )
    (net (code "55") (name "unconnected-(U1-XO-Pad45)") (class "Default")
      (node (ref "U1") (pin "45") (pinfunction "XO_45") (pintype "output+no_connect"))
    )
  )
)
